# Sheet1.net
KiCad netlist of a schematic drawn in Altium Designer
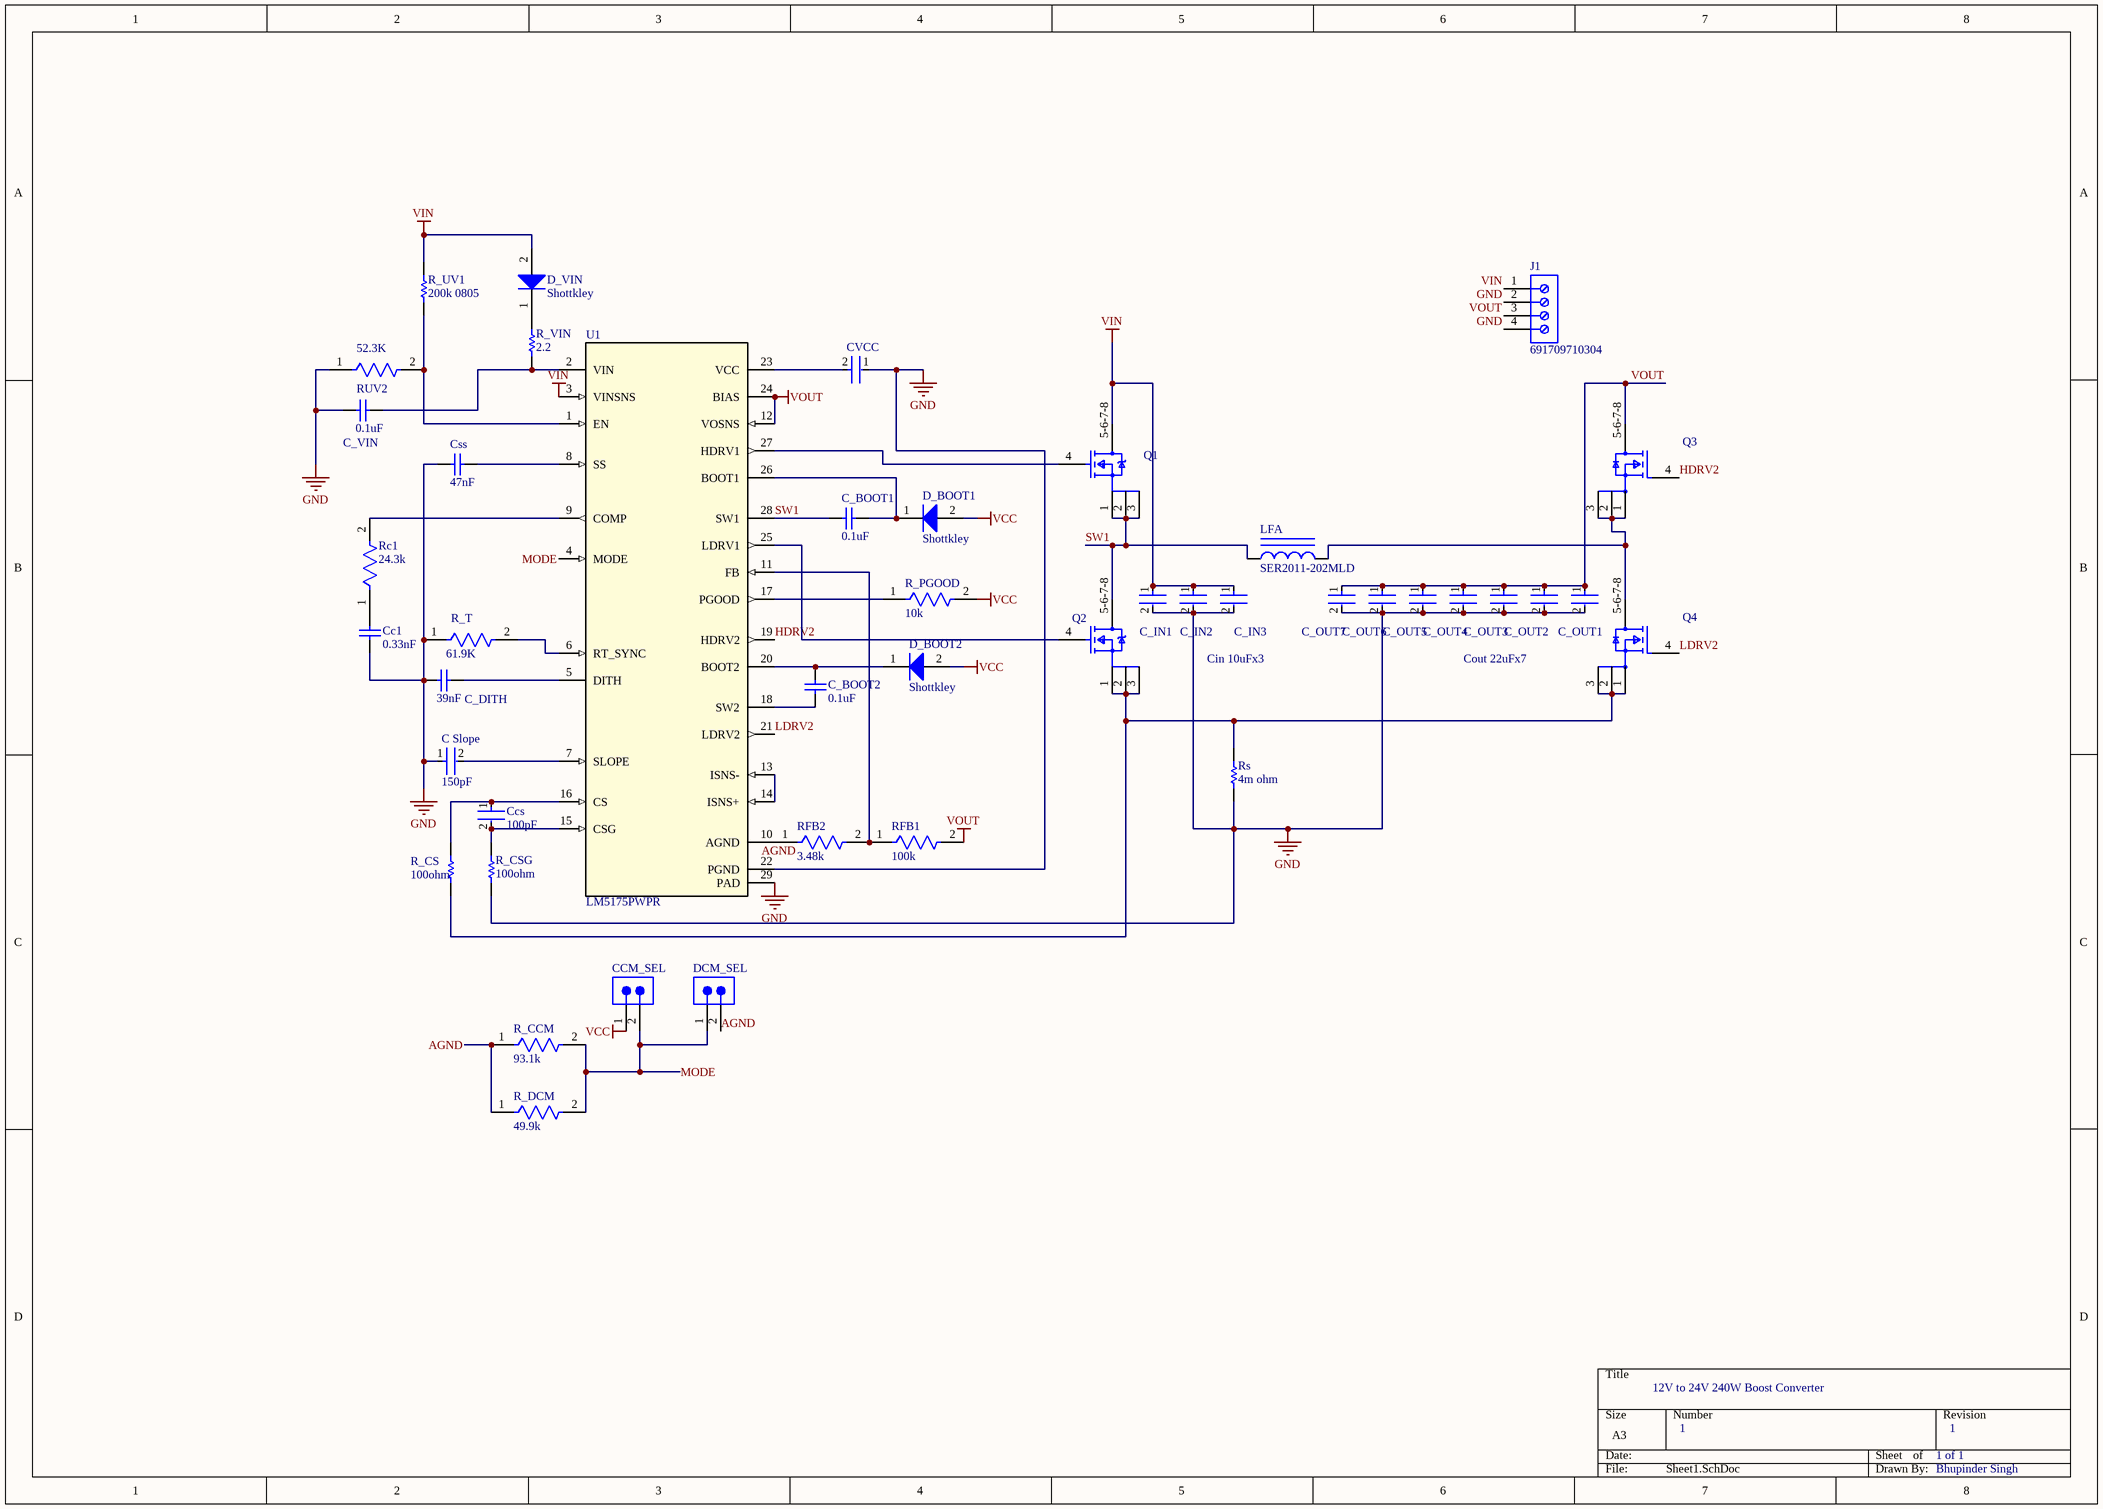
[diagram p0: Sheet1.SchDoc]

(export (version "E")
  (design (tool "Eeschema 10.0.6"))
  (components
    (comp (ref "52.3K")
      (value "RUV2")
      (footprint "FP-RG2012-IPC_A")
      (description "Automotive Metal Thin Film Chip Resistor, 0805, 52.3kΩ, 0.1%, 25ppm/°C, 0.125W, 150V")
      (fields (field (name "TOLERANCE") "0.1%"))
      (libsource (lib "Altium Content Vault") (part "1029c3af85768c4190bb7ad29bc67b5"))
    )
    (comp (ref "C Slope")
      (value "150pF")
      (footprint "FP-0805-L_2_01_0_2-W_1_25-IPC_B")
      (description "General Purpose Ceramic Capacitor, 0805, 150pF, 5%, C0G, 30ppm/°C, 200V")
      (fields (field (name "TOLERANCE") "5%") (field (name "VOLTAGE") "200V"))
      (libsource (lib "Altium Content Vault") (part "02cd4be3c70576c341d710602a673aa"))
    )
    (comp (ref "Cc1")
      (value "0.33nF")
      (footprint "CAPC1608X92X38LL15T08")
      (fields (field (name "MANUFACTURER") "Vitramon") (field (name "PART NUMBER") "VJ0603D331KXAAJ"))
      (libsource (lib "Altium Content Vault") (part "CAP"))
    )
    (comp (ref "CCM_SEL")
      (value "61300211121")
      (footprint "61300211121")
      (libsource (lib "Altium Content Vault") (part "Header_Male_1R_02P"))
    )
    (comp (ref "Ccs")
      (value "100pF")
      (footprint "FP-C0805C-DN-MFG")
      (description "CAP CER 100PF 100V C0G/NP0 0805")
      (fields
        (field (name "MANUFACTURER") "KEMET")
        (field (name "MANUFACTURER PART NUMBER") "C0805C101J1GACTU")
      )
      (libsource (lib "Altium Content Vault") (part "b4654b650e69147ec39a6b967a45e02"))
    )
    (comp (ref "Css")
      (value "47nF")
      (footprint "CAPC1608X90X35NL15T15")
      (fields
        (field (name "PART NUMBER") "06035C473KAZ2A")
        (field (name "MANUFACTURER") "AVX Interconnect / Elco")
      )
      (libsource (lib "Altium Content Vault") (part "CAP"))
    )
    (comp (ref "CVCC")
      (value "C1608X5R1H105K080AB")
      (footprint "FP-C1608-080-0_1-IPC_B")
      (description "Multilayer Ceramic Capacitors 1μF ±10% 50V X5R SMD 0603")
      (fields (field (name "VOLTAGE") "50V") (field (name "TOLERANCE") "10%"))
      (libsource (lib "Altium Content Vault") (part "236180d848d6139a670b325ea6854c9"))
    )
    (comp (ref "C_BOOT1")
      (value "0.1uF")
      (footprint "CAPC1608X90X35ML10T15")
      (description "Chip Capacitor, 0.1 uF, +/- 10%, 50 V, -55 to 125 degC, 0603 (1608 Metric), RoHS, Tape and Reel")
      (fields (field (name "TOLERANCE") "10%") (field (name "VOLTAGE") "50V"))
      (libsource (lib "Altium Content Vault") (part "CAP-NP-2"))
    )
    (comp (ref "C_BOOT2")
      (value "0.1uF")
      (footprint "CAPC1608X90X35ML10T15")
      (description "Chip Capacitor, 0.1 uF, +/- 10%, 50 V, -55 to 125 degC, 0603 (1608 Metric), RoHS, Tape and Reel")
      (fields (field (name "TOLERANCE") "10%") (field (name "VOLTAGE") "50V"))
      (libsource (lib "Altium Content Vault") (part "CAP-NP-2"))
    )
    (comp (ref "C_DITH")
      (value "39nF")
      (footprint "CAPC1608X90X35NL15T15")
      (fields
        (field (name "MANUFACTURER") "AVX Interconnect / Elco")
        (field (name "PART NUMBER") "06035C393KAT2A")
      )
      (libsource (lib "Altium Content Vault") (part "CAP"))
    )
    (comp (ref "C_IN1")
      (value "C0805C106K8PACTU")
      (footprint "FP-C0805C-DG-MFG")
      (description "CAP CER 10UF 10V X5R 0805")
      (fields (field (name "TOLERANCE") "10%") (field (name "MANUFACTURER") "Kemet"))
      (libsource (lib "Altium Content Vault") (part "11868f565c42a9108669ba33697ecf6"))
    )
    (comp (ref "C_IN2")
      (value "C0805C106K8PACTU")
      (footprint "FP-C0805C-DG-MFG")
      (description "CAP CER 10UF 10V X5R 0805")
      (fields (field (name "TOLERANCE") "10%") (field (name "MANUFACTURER") "Kemet"))
      (libsource (lib "Altium Content Vault") (part "11868f565c42a9108669ba33697ecf6"))
    )
    (comp (ref "C_IN3")
      (value "C0805C106K8PACTU")
      (footprint "FP-C0805C-DG-MFG")
      (description "CAP CER 10UF 10V X5R 0805")
      (fields (field (name "TOLERANCE") "10%") (field (name "MANUFACTURER") "Kemet"))
      (libsource (lib "Altium Content Vault") (part "11868f565c42a9108669ba33697ecf6"))
    )
    (comp (ref "C_OUT1")
      (value "GRM21BR60J226ME39L")
      (footprint "FP-GRM21B-0_15-MFG")
      (description "Chip Multilayer Ceramic Capacitors for General Purpose, 0805, 22uF, X5R, 15%, 20%, 6.3V")
      (fields (field (name "VOLTAGE") "6.3V") (field (name "TOLERANCE") "20%"))
      (libsource (lib "Altium Content Vault") (part "b4654b650e69147ec39a6b967a45e02"))
    )
    (comp (ref "C_OUT2")
      (value "GRM21BR60J226ME39L")
      (footprint "FP-GRM21B-0_15-MFG")
      (description "Chip Multilayer Ceramic Capacitors for General Purpose, 0805, 22uF, X5R, 15%, 20%, 6.3V")
      (fields (field (name "VOLTAGE") "6.3V") (field (name "TOLERANCE") "20%"))
      (libsource (lib "Altium Content Vault") (part "b4654b650e69147ec39a6b967a45e02"))
    )
    (comp (ref "C_OUT3")
      (value "GRM21BR60J226ME39L")
      (footprint "FP-GRM21B-0_15-MFG")
      (description "Chip Multilayer Ceramic Capacitors for General Purpose, 0805, 22uF, X5R, 15%, 20%, 6.3V")
      (fields (field (name "VOLTAGE") "6.3V") (field (name "TOLERANCE") "20%"))
      (libsource (lib "Altium Content Vault") (part "b4654b650e69147ec39a6b967a45e02"))
    )
    (comp (ref "C_OUT4")
      (value "GRM21BR60J226ME39L")
      (footprint "FP-GRM21B-0_15-MFG")
      (description "Chip Multilayer Ceramic Capacitors for General Purpose, 0805, 22uF, X5R, 15%, 20%, 6.3V")
      (fields (field (name "VOLTAGE") "6.3V") (field (name "TOLERANCE") "20%"))
      (libsource (lib "Altium Content Vault") (part "b4654b650e69147ec39a6b967a45e02"))
    )
    (comp (ref "C_OUT5")
      (value "GRM21BR60J226ME39L")
      (footprint "FP-GRM21B-0_15-MFG")
      (description "Chip Multilayer Ceramic Capacitors for General Purpose, 0805, 22uF, X5R, 15%, 20%, 6.3V")
      (fields (field (name "VOLTAGE") "6.3V") (field (name "TOLERANCE") "20%"))
      (libsource (lib "Altium Content Vault") (part "b4654b650e69147ec39a6b967a45e02"))
    )
    (comp (ref "C_OUT6")
      (value "GRM21BR60J226ME39L")
      (footprint "FP-GRM21B-0_15-MFG")
      (description "Chip Multilayer Ceramic Capacitors for General Purpose, 0805, 22uF, X5R, 15%, 20%, 6.3V")
      (fields (field (name "VOLTAGE") "6.3V") (field (name "TOLERANCE") "20%"))
      (libsource (lib "Altium Content Vault") (part "b4654b650e69147ec39a6b967a45e02"))
    )
    (comp (ref "C_OUT7")
      (value "GRM21BR60J226ME39L")
      (footprint "FP-GRM21B-0_15-MFG")
      (description "Chip Multilayer Ceramic Capacitors for General Purpose, 0805, 22uF, X5R, 15%, 20%, 6.3V")
      (fields (field (name "VOLTAGE") "6.3V") (field (name "TOLERANCE") "20%"))
      (libsource (lib "Altium Content Vault") (part "b4654b650e69147ec39a6b967a45e02"))
    )
    (comp (ref "C_VIN")
      (value "0.1uF")
      (footprint "CAPC1608X90X35ML10T15")
      (description "Chip Capacitor, 0.1 uF, +/- 10%, 50 V, -55 to 125 degC, 0603 (1608 Metric), RoHS, Tape and Reel")
      (fields (field (name "TOLERANCE") "10%") (field (name "VOLTAGE") "50V"))
      (libsource (lib "Altium Content Vault") (part "CAP-NP-2"))
    )
    (comp (ref "DCM_SEL")
      (value "61300211121")
      (footprint "61300211121")
      (libsource (lib "Altium Content Vault") (part "Header_Male_1R_02P"))
    )
    (comp (ref "D_BOOT1")
      (value "Shottkley")
      (footprint "ONSC-SOD-323-2-477-02_V")
      (description "Schottky Barrier Diode, 2-Pin SOD-323, Pb-Free, Tape and Reel")
      (fields (field (name "PARTNUMBER") "BAT54HT1G") (field (name "MANUFACTURER") "On Semiconductor"))
      (libsource (lib "Altium Content Vault") (part "ONSC-D-K1A2-2"))
    )
    (comp (ref "D_BOOT2")
      (value "Shottkley")
      (footprint "ONSC-SOD-323-2-477-02_V")
      (description "Schottky Barrier Diode, 2-Pin SOD-323, Pb-Free, Tape and Reel")
      (fields (field (name "PARTNUMBER") "BAT54HT1G") (field (name "MANUFACTURER") "On Semiconductor"))
      (libsource (lib "Altium Content Vault") (part "ONSC-D-K1A2-2"))
    )
    (comp (ref "D_VIN")
      (value "Shottkley")
      (footprint "ONSC-SOD-323-2-477-02_V")
      (description "Schottky Barrier Diode, 2-Pin SOD-323, Pb-Free, Tape and Reel")
      (fields (field (name "PARTNUMBER") "BAT54HT1G") (field (name "MANUFACTURER") "On Semiconductor"))
      (libsource (lib "Altium Content Vault") (part "ONSC-D-K1A2-2"))
    )
    (comp (ref "J1")
      (value "691709710304")
      (footprint "691709710304")
      (fields (field (name "VOLTAGE") "300V"))
      (libsource (lib "Altium Content Vault") (part "TBL - 1R - 04P - Screw"))
    )
    (comp (ref "LF")
      (value "SER2011-202MLD")
      (footprint "COIL-SER2011-3_V")
      (fields (field (name "MANUFACTURER") "Coilcraft"))
      (libsource (lib "Altium Content Vault") (part "COIL-SER20XX-3"))
    )
    (comp (ref "Q1")
      (value "CSD18563Q5A")
      (footprint "FP-DQJ0008A-MFG")
      (description "MOSFET N-CH 60V 100A 8SON")
      (fields
        (field (name "MANUFACTURER") "Texas Instruments")
        (field (name "OCTOPART") "https://octopart.com/csd18563q5a-texas+instruments-30331677")
      )
      (libsource (lib "Altium Content Vault") (part "1f414301ec49d946f73eb09675df2e7"))
    )
    (comp (ref "Q2")
      (value "CSD18563Q5A")
      (footprint "FP-DQJ0008A-MFG")
      (description "MOSFET N-CH 60V 100A 8SON")
      (fields
        (field (name "MANUFACTURER") "Texas Instruments")
        (field (name "OCTOPART") "https://octopart.com/csd18563q5a-texas+instruments-30331677")
      )
      (libsource (lib "Altium Content Vault") (part "1f414301ec49d946f73eb09675df2e7"))
    )
    (comp (ref "Q3")
      (value "CSD16321Q5")
      (footprint "FP-DQH0008A-0")
      (description "MOSFET N-CH 25V 31A/100A 8VSON")
      (libsource (lib "Altium Content Vault") (part "84ec0f3579654814e84742019f72fd3"))
    )
    (comp (ref "Q4")
      (value "CSD16321Q5")
      (footprint "FP-DQH0008A-0")
      (description "MOSFET N-CH 25V 31A/100A 8VSON")
      (libsource (lib "Altium Content Vault") (part "84ec0f3579654814e84742019f72fd3"))
    )
    (comp (ref "Rc1")
      (value "24.3k")
      (footprint "FP-CR1206-MFG")
      (description "Thick Film Chip Resistors 1206 24.3kΩ 0.25W 1% 100ppm/°C")
      (fields (field (name "TOLERANCE") "1%"))
      (libsource (lib "Altium Content Vault") (part "1029c3af85768c4190bb7ad29bc67b5"))
    )
    (comp (ref "RFB1")
      (value "100k")
      (footprint "FP-RC0603-0_55-MFG")
      (description "RES SMD 100K OHM 1% 1/10W 0603")
      (fields (field (name "TOLERANCE") "1%"))
      (libsource (lib "Altium Content Vault") (part "1029c3af85768c4190bb7ad29bc67b5"))
    )
    (comp (ref "RFB2")
      (value "3.48k")
      (footprint "FP-ERA3A-IPC_A")
      (description "RES SMD 3.48KOHM 0.1% 1/10W 0603")
      (fields (field (name "TOLERANCE") "0.1%"))
      (libsource (lib "Altium Content Vault") (part "1029c3af85768c4190bb7ad29bc67b5"))
    )
    (comp (ref "Rs")
      (value "4m ohm")
      (fields (field (name "Comment") "Resistor"))
      (libsource (lib "Simulation Generic Components") (part "Resistor"))
    )
    (comp (ref "R_CCM")
      (value "93.1k")
      (footprint "FP-RN732A-MFG")
      (description "SMD Chip Resistor, Thin Film, 93.1KΩ, 100 V, 0805 [2012 Metric], 100 mW, 0.1%, RN73 Series")
      (fields
        (field (name "MANUFACTURER PART NUMBER") "RN73C2A93K1BTDF")
        (field (name "MANUFACTURER") "TE Connectivity")
      )
      (libsource (lib "Altium Content Vault") (part "1029c3af85768c4190bb7ad29bc67b5"))
    )
    (comp (ref "R_CS")
      (value "100ohm")
      (footprint "RESC1608X55X30LL15T15")
      (fields (field (name "MANUFACTURER") "Panasonic") (field (name "PART NUMBER") "ERJ-3EKF1000V"))
      (libsource (lib "Altium Content Vault") (part "RES"))
    )
    (comp (ref "R_CSG")
      (value "100ohm")
      (footprint "RESC1608X55X30LL15T15")
      (fields (field (name "MANUFACTURER") "Panasonic") (field (name "PART NUMBER") "ERJ-3EKF1000V"))
      (libsource (lib "Altium Content Vault") (part "RES"))
    )
    (comp (ref "R_DCM")
      (value "49.9k")
      (footprint "FP-CRCW0805-e3-IPC_C")
      (description "RES Thick Film, 49.9kΩ, 1%, 0.125W, 100ppm/°C, 0805")
      (fields (field (name "TOLERANCE") "1%"))
      (libsource (lib "Altium Content Vault") (part "1029c3af85768c4190bb7ad29bc67b5"))
    )
    (comp (ref "R_PGOOD")
      (value "10k")
      (footprint "FP-RR0510-MFG")
      (description "20kΩ ±0.5% 0.0625W 1/16W Chip Resistor 0402 (1005 Metric) Thin Film")
      (fields (field (name "TOLERANCE") "0.5%"))
      (libsource (lib "Altium Content Vault") (part "1029c3af85768c4190bb7ad29bc67b5"))
    )
    (comp (ref "R_T")
      (value "61.9K")
      (footprint "FP-RG2012-IPC_A")
      (description "Automotive Metal Thin Film Chip Resistor, 0805, 61.9kΩ, 0.5%, 25ppm/°C, 0.125W, 150V")
      (fields (field (name "TOLERANCE") "0.5%"))
      (libsource (lib "Altium Content Vault") (part "1029c3af85768c4190bb7ad29bc67b5"))
    )
    (comp (ref "R_UV1")
      (value "200k 0805")
      (footprint "RESC2013X70X40LL20T20")
      (fields (field (name "MANUFACTURER") "Panasonic") (field (name "PART NUMBER") "ERJ-6ENF2003V"))
      (libsource (lib "Altium Content Vault") (part "RES"))
    )
    (comp (ref "R_VIN")
      (value "2.2")
      (footprint "RESC1609X50X30LL10T20")
      (fields (field (name "PART NUMBER") "CRCW06032R20FNEA") (field (name "MANUFACTURER") "Vishay Dale"))
      (libsource (lib "Altium Content Vault") (part "RES"))
    )
    (comp (ref "U1")
      (value "LM5175PWPR")
      (footprint "PWP0028F_N")
      (description "No Description Available")
      (fields (field (name "PARTNUMBER") "LM5175PWP") (field (name "MANUFACTURER") "Texas Instruments"))
      (libsource (lib "LM5175PWPR") (part "LM5175PWPR"))
    )
  )
  (nets
    (net (code "1") (name "/AGND") (class "Default")
      (node (ref "DCM_SEL") (pin "2") (pinfunction "2_2") (pintype "passive"))
      (node (ref "R_CCM") (pin "1") (pinfunction "1_1") (pintype "passive"))
      (node (ref "R_DCM") (pin "1") (pinfunction "1_1") (pintype "passive"))
    )
    (net (code "2") (name "/HDRV2") (class "Default")
      (node (ref "Q3") (pin "4") (pinfunction "G_4") (pintype "passive"))
      (node (ref "U1") (pin "19") (pinfunction "HDRV2_19") (pintype "output"))
    )
    (net (code "3") (name "/LDRV2") (class "Default")
      (node (ref "Q4") (pin "4") (pinfunction "G_4") (pintype "passive"))
      (node (ref "U1") (pin "21") (pinfunction "LDRV2_21") (pintype "output"))
    )
    (net (code "4") (name "/MODE") (class "Default")
      (node (ref "CCM_SEL") (pin "2") (pinfunction "2_2") (pintype "passive"))
      (node (ref "DCM_SEL") (pin "1") (pinfunction "1_1") (pintype "passive"))
      (node (ref "R_CCM") (pin "2") (pinfunction "2_2") (pintype "passive"))
      (node (ref "R_DCM") (pin "2") (pinfunction "2_2") (pintype "passive"))
      (node (ref "U1") (pin "4") (pinfunction "MODE_4") (pintype "input"))
    )
    (net (code "5") (name "/SW1") (class "Default")
      (node (ref "C_BOOT1") (pin "1") (pinfunction "1_1") (pintype "passive"))
      (node (ref "LF") (pin "1") (pinfunction "1_1") (pintype "passive"))
      (node (ref "Q1") (pin "1") (pinfunction "S_1") (pintype "passive"))
      (node (ref "Q1") (pin "2") (pinfunction "S_2") (pintype "passive"))
      (node (ref "Q1") (pin "3") (pinfunction "S_3") (pintype "passive"))
      (node (ref "Q2") (pin "5-6-7-8") (pinfunction "D_5-6-7-8") (pintype "passive"))
      (node (ref "U1") (pin "28") (pinfunction "SW1_28") (pintype "power_in"))
    )
    (net (code "6") (name "GND") (class "Default")
      (node (ref "52.3K") (pin "1") (pinfunction "1_1") (pintype "passive"))
      (node (ref "C Slope") (pin "1") (pinfunction "1_1") (pintype "passive"))
      (node (ref "CVCC") (pin "1") (pinfunction "1_1") (pintype "passive"))
      (node (ref "C_DITH") (pin "1") (pinfunction "1_1") (pintype "passive"))
      (node (ref "C_IN1") (pin "2") (pinfunction "2_2") (pintype "passive"))
      (node (ref "C_IN2") (pin "2") (pinfunction "2_2") (pintype "passive"))
      (node (ref "C_IN3") (pin "2") (pinfunction "2_2") (pintype "passive"))
      (node (ref "C_OUT1") (pin "2") (pinfunction "2_2") (pintype "passive"))
      (node (ref "C_OUT2") (pin "2") (pinfunction "2_2") (pintype "passive"))
      (node (ref "C_OUT3") (pin "2") (pinfunction "2_2") (pintype "passive"))
      (node (ref "C_OUT4") (pin "2") (pinfunction "2_2") (pintype "passive"))
      (node (ref "C_OUT5") (pin "2") (pinfunction "2_2") (pintype "passive"))
      (node (ref "C_OUT6") (pin "2") (pinfunction "2_2") (pintype "passive"))
      (node (ref "C_OUT7") (pin "2") (pinfunction "2_2") (pintype "passive"))
      (node (ref "C_VIN") (pin "1") (pinfunction "1_1") (pintype "passive"))
      (node (ref "Cc1") (pin "1") (pinfunction "1_1") (pintype "passive"))
      (node (ref "Css") (pin "1") (pinfunction "1_1") (pintype "passive"))
      (node (ref "J1") (pin "2") (pinfunction "2_2") (pintype "passive"))
      (node (ref "J1") (pin "4") (pinfunction "4_4") (pintype "passive"))
      (node (ref "R_CSG") (pin "1") (pinfunction "1_1") (pintype "passive"))
      (node (ref "R_T") (pin "1") (pinfunction "1_1") (pintype "passive"))
      (node (ref "Rs") (pin "1") (pinfunction "1_1") (pintype "passive"))
      (node (ref "U1") (pin "22") (pinfunction "PGND_22") (pintype "power_in"))
      (node (ref "U1") (pin "29") (pinfunction "PAD_29") (pintype "power_in"))
    )
    (net (code "7") (name "Net-(Cc1-Pad2)") (class "Default")
      (node (ref "Cc1") (pin "2") (pinfunction "2_2") (pintype "passive"))
      (node (ref "Rc1") (pin "1") (pinfunction "1_1") (pintype "passive"))
    )
    (net (code "8") (name "Net-(D_BOOT1-K)") (class "Default")
      (node (ref "C_BOOT1") (pin "2") (pinfunction "2_2") (pintype "passive"))
      (node (ref "D_BOOT1") (pin "1") (pinfunction "K_1") (pintype "passive"))
      (node (ref "U1") (pin "26") (pinfunction "BOOT1_26") (pintype "power_in"))
    )
    (net (code "9") (name "Net-(D_BOOT2-K)") (class "Default")
      (node (ref "C_BOOT2") (pin "1") (pinfunction "1_1") (pintype "passive"))
      (node (ref "D_BOOT2") (pin "1") (pinfunction "K_1") (pintype "passive"))
      (node (ref "U1") (pin "20") (pinfunction "BOOT2_20") (pintype "power_in"))
    )
    (net (code "10") (name "Net-(D_VIN-K)") (class "Default")
      (node (ref "D_VIN") (pin "1") (pinfunction "K_1") (pintype "passive"))
      (node (ref "R_VIN") (pin "2") (pinfunction "2_2") (pintype "passive"))
    )
    (net (code "11") (name "Net-(Q1-G)") (class "Default")
      (node (ref "Q1") (pin "4") (pinfunction "G_4") (pintype "passive"))
      (node (ref "U1") (pin "27") (pinfunction "HDRV1_27") (pintype "output"))
    )
    (net (code "12") (name "Net-(Q2-G)") (class "Default")
      (node (ref "Q2") (pin "4") (pinfunction "G_4") (pintype "passive"))
      (node (ref "U1") (pin "25") (pinfunction "LDRV1_25") (pintype "output"))
    )
    (net (code "13") (name "Net-(Q2-S-Pad1)") (class "Default")
      (node (ref "Q2") (pin "1") (pinfunction "S_1") (pintype "passive"))
      (node (ref "Q2") (pin "2") (pinfunction "S_2") (pintype "passive"))
      (node (ref "Q2") (pin "3") (pinfunction "S_3") (pintype "passive"))
      (node (ref "Q4") (pin "1") (pinfunction "S_1") (pintype "passive"))
      (node (ref "Q4") (pin "2") (pinfunction "S_2") (pintype "passive"))
      (node (ref "Q4") (pin "3") (pinfunction "S_3") (pintype "passive"))
      (node (ref "R_CS") (pin "1") (pinfunction "1_1") (pintype "passive"))
      (node (ref "Rs") (pin "2") (pinfunction "2_2") (pintype "passive"))
    )
    (net (code "14") (name "Net-(Q4-D)") (class "Default")
      (node (ref "LF") (pin "2") (pinfunction "2_2") (pintype "passive"))
      (node (ref "Q3") (pin "1") (pinfunction "S_1") (pintype "passive"))
      (node (ref "Q3") (pin "2") (pinfunction "S_2") (pintype "passive"))
      (node (ref "Q3") (pin "3") (pinfunction "S_3") (pintype "passive"))
      (node (ref "Q4") (pin "5-6-7-8") (pinfunction "D_5-6-7-8") (pintype "passive"))
    )
    (net (code "15") (name "Net-(U1-AGND)") (class "Default")
      (node (ref "RFB2") (pin "1") (pinfunction "1_1") (pintype "passive"))
      (node (ref "U1") (pin "10") (pinfunction "AGND_10") (pintype "power_in"))
    )
    (net (code "16") (name "Net-(U1-COMP)") (class "Default")
      (node (ref "Rc1") (pin "2") (pinfunction "2_2") (pintype "passive"))
      (node (ref "U1") (pin "9") (pinfunction "COMP_9") (pintype "output"))
    )
    (net (code "17") (name "Net-(U1-CS)") (class "Default")
      (node (ref "Ccs") (pin "1") (pinfunction "1_1") (pintype "passive"))
      (node (ref "R_CS") (pin "2") (pinfunction "2_2") (pintype "passive"))
      (node (ref "U1") (pin "16") (pinfunction "CS_16") (pintype "input"))
    )
    (net (code "18") (name "Net-(U1-CSG)") (class "Default")
      (node (ref "Ccs") (pin "2") (pinfunction "2_2") (pintype "passive"))
      (node (ref "R_CSG") (pin "2") (pinfunction "2_2") (pintype "passive"))
      (node (ref "U1") (pin "15") (pinfunction "CSG_15") (pintype "input"))
    )
    (net (code "19") (name "Net-(U1-DITH)") (class "Default")
      (node (ref "C_DITH") (pin "2") (pinfunction "2_2") (pintype "passive"))
      (node (ref "U1") (pin "5") (pinfunction "DITH_5") (pintype "passive"))
    )
    (net (code "20") (name "Net-(U1-EN)") (class "Default")
      (node (ref "52.3K") (pin "2") (pinfunction "2_2") (pintype "passive"))
      (node (ref "R_UV1") (pin "1") (pinfunction "1_1") (pintype "passive"))
      (node (ref "U1") (pin "1") (pinfunction "EN_1") (pintype "input"))
    )
    (net (code "21") (name "Net-(U1-FB)") (class "Default")
      (node (ref "RFB1") (pin "1") (pinfunction "1_1") (pintype "passive"))
      (node (ref "RFB2") (pin "2") (pinfunction "2_2") (pintype "passive"))
      (node (ref "U1") (pin "11") (pinfunction "FB_11") (pintype "input"))
    )
    (net (code "22") (name "Net-(U1-ISNS+)") (class "Default")
      (node (ref "U1") (pin "13") (pinfunction "ISNS-_13") (pintype "input"))
      (node (ref "U1") (pin "14") (pinfunction "ISNS+_14") (pintype "input"))
    )
    (net (code "23") (name "Net-(U1-PGOOD)") (class "Default")
      (node (ref "R_PGOOD") (pin "1") (pinfunction "1_1") (pintype "passive"))
      (node (ref "U1") (pin "17") (pinfunction "PGOOD_17") (pintype "output"))
    )
    (net (code "24") (name "Net-(U1-RT_SYNC)") (class "Default")
      (node (ref "R_T") (pin "2") (pinfunction "2_2") (pintype "passive"))
      (node (ref "U1") (pin "6") (pinfunction "RT_SYNC_6") (pintype "input"))
    )
    (net (code "25") (name "Net-(U1-SLOPE)") (class "Default")
      (node (ref "C Slope") (pin "2") (pinfunction "2_2") (pintype "passive"))
      (node (ref "U1") (pin "7") (pinfunction "SLOPE_7") (pintype "input"))
    )
    (net (code "26") (name "Net-(U1-SS)") (class "Default")
      (node (ref "Css") (pin "2") (pinfunction "2_2") (pintype "passive"))
      (node (ref "U1") (pin "8") (pinfunction "SS_8") (pintype "input"))
    )
    (net (code "27") (name "Net-(U1-SW2)") (class "Default")
      (node (ref "C_BOOT2") (pin "2") (pinfunction "2_2") (pintype "passive"))
      (node (ref "U1") (pin "18") (pinfunction "SW2_18") (pintype "power_in"))
    )
    (net (code "28") (name "Net-(U1-VCC)") (class "Default")
      (node (ref "CVCC") (pin "2") (pinfunction "2_2") (pintype "passive"))
      (node (ref "U1") (pin "23") (pinfunction "VCC_23") (pintype "power_in"))
    )
    (net (code "29") (name "Net-(U1-VIN)") (class "Default")
      (node (ref "C_VIN") (pin "2") (pinfunction "2_2") (pintype "passive"))
      (node (ref "R_VIN") (pin "1") (pinfunction "1_1") (pintype "passive"))
      (node (ref "U1") (pin "2") (pinfunction "VIN_2") (pintype "power_in"))
    )
    (net (code "30") (name "VCC") (class "Default")
      (node (ref "CCM_SEL") (pin "1") (pinfunction "1_1") (pintype "passive"))
      (node (ref "D_BOOT1") (pin "2") (pinfunction "A_2") (pintype "passive"))
      (node (ref "D_BOOT2") (pin "2") (pinfunction "A_2") (pintype "passive"))
      (node (ref "R_PGOOD") (pin "2") (pinfunction "2_2") (pintype "passive"))
    )
    (net (code "31") (name "VIN") (class "Default")
      (node (ref "C_IN1") (pin "1") (pinfunction "1_1") (pintype "passive"))
      (node (ref "C_IN2") (pin "1") (pinfunction "1_1") (pintype "passive"))
      (node (ref "C_IN3") (pin "1") (pinfunction "1_1") (pintype "passive"))
      (node (ref "D_VIN") (pin "2") (pinfunction "A_2") (pintype "passive"))
      (node (ref "J1") (pin "1") (pinfunction "1_1") (pintype "passive"))
      (node (ref "Q1") (pin "5-6-7-8") (pinfunction "D_5-6-7-8") (pintype "passive"))
      (node (ref "R_UV1") (pin "2") (pinfunction "2_2") (pintype "passive"))
      (node (ref "U1") (pin "3") (pinfunction "VINSNS_3") (pintype "input"))
    )
    (net (code "32") (name "VOUT") (class "Default")
      (node (ref "C_OUT1") (pin "1") (pinfunction "1_1") (pintype "passive"))
      (node (ref "C_OUT2") (pin "1") (pinfunction "1_1") (pintype "passive"))
      (node (ref "C_OUT3") (pin "1") (pinfunction "1_1") (pintype "passive"))
      (node (ref "C_OUT4") (pin "1") (pinfunction "1_1") (pintype "passive"))
      (node (ref "C_OUT5") (pin "1") (pinfunction "1_1") (pintype "passive"))
      (node (ref "C_OUT6") (pin "1") (pinfunction "1_1") (pintype "passive"))
      (node (ref "C_OUT7") (pin "1") (pinfunction "1_1") (pintype "passive"))
      (node (ref "J1") (pin "3") (pinfunction "3_3") (pintype "passive"))
      (node (ref "Q3") (pin "5-6-7-8") (pinfunction "D_5-6-7-8") (pintype "passive"))
      (node (ref "RFB1") (pin "2") (pinfunction "2_2") (pintype "passive"))
      (node (ref "U1") (pin "12") (pinfunction "VOSNS_12") (pintype "input"))
      (node (ref "U1") (pin "24") (pinfunction "BIAS_24") (pintype "power_in"))
    )
  )
)
